# RELAYBOARD.net
KiCad netlist of a schematic drawn in Altium Designer
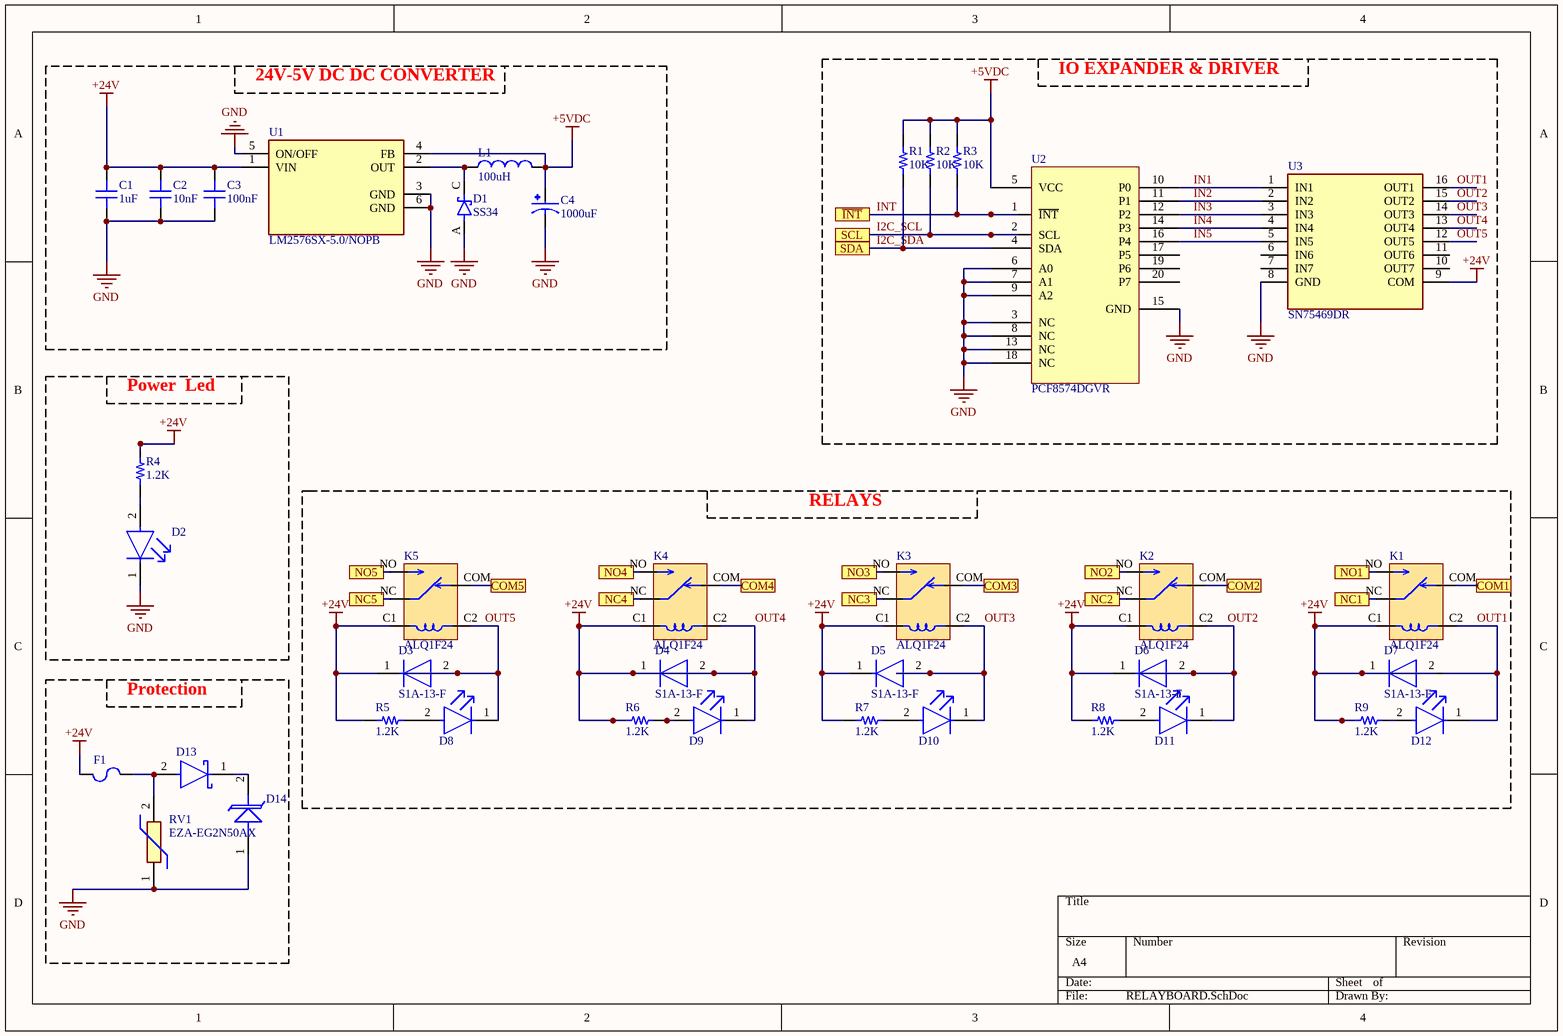
[diagram p0: RELAYBOARD.SchDoc]

(export (version "E")
  (design (tool "Eeschema 10.0.6"))
  (components
    (comp (ref "C1")
      (value "1uF")
      (footprint "CAP-0603")
      (description "Cap Ceramic 1uF 50V X5R 20% Pad SMD 0603 85C Low ESR Automotive T/R")
      (fields
        (field (name "MANUFACTURER") "Taiyo Yuden")
        (field (name "MANUFACTURER PART NUMBER") "UMK107ABJ105MAHT")
      )
      (libsource (lib "Schlib1") (part "UMK107ABJ105MAHT"))
    )
    (comp (ref "C2")
      (value "10nF")
      (footprint "CAP-0603")
      (description "Cap Ceramic 0.01uF 50V X7R 20% SMD 0603 125°C Paper T/R")
      (fields
        (field (name "MANUFACTURER") "KEMET")
        (field (name "MANUFACTURER PART NUMBER") "C0603C103M5RAC7411")
      )
      (libsource (lib "Schlib1") (part "C0603C103M5RAC7411"))
    )
    (comp (ref "C3")
      (value "100nF")
      (footprint "CAP-0603")
      (description "Cap Ceramic 0.1uF 50V X7R 10% SMD 0603 125°C Paper T/R 100nF")
      (fields
        (field (name "MANUFACTURER") "KEMET")
        (field (name "MANUFACTURER PART NUMBER") "C0603C104K5RAC7411")
      )
      (libsource (lib "Schlib1") (part "C0603C104K5RAC7411"))
    )
    (comp (ref "C4")
      (value "1000uF")
      (footprint "CAP RADIAL 1000UF")
      (description "Cap Aluminum Lytic 1000uF 25V 20% (18 X 16.5mm) SMD 0.075 Ohm 1300mA 2000h 125C Automotive T/R")
      (fields
        (field (name "MANUFACTURER") "Panasonic")
        (field (name "MANUFACTURER PART NUMBER") "EEE-TK1E102AM")
      )
      (libsource (lib "Schlib1") (part "EEETK1E102AM"))
    )
    (comp (ref "D1")
      (value "SS34")
      (footprint "SS34")
      (description "SS Series 500 mV 3 A 40 V Max Reverse Voltage Schottky Rectifier - DO-214AB")
      (fields (field (name "MANUFACTURER") "ON Semiconductor / Fairchild") (field (name "VOLTAGE") "40V"))
      (libsource (lib "Schlib1") (part "SS34"))
    )
    (comp (ref "D2")
      (value "LS R976-NR-1")
      (footprint "LS R976-NR-1")
      (description "Led SMT Red 0805 Tape")
      (fields
        (field (name "MANUFACTURER") "Osram Opto")
        (field (name "MANUFACTURER PART NUMBER") "LSR976-NR-1")
      )
      (libsource (lib "Schlib1") (part "LS R976-NR-1"))
    )
    (comp (ref "D3")
      (value "S1A-13-F")
      (footprint "S1A-13-F")
      (description "VR=50V IF=1A 10pF Trr=3us")
      (fields (field (name "MANUFACTURER") "Diodes"))
      (libsource (lib "Schlib1") (part "S1A-13-F"))
    )
    (comp (ref "D4")
      (value "S1A-13-F")
      (footprint "S1A-13-F")
      (description "VR=50V IF=1A 10pF Trr=3us")
      (fields (field (name "MANUFACTURER") "Diodes"))
      (libsource (lib "Schlib1") (part "S1A-13-F"))
    )
    (comp (ref "D5")
      (value "S1A-13-F")
      (footprint "S1A-13-F")
      (description "VR=50V IF=1A 10pF Trr=3us")
      (fields (field (name "MANUFACTURER") "Diodes"))
      (libsource (lib "Schlib1") (part "S1A-13-F"))
    )
    (comp (ref "D6")
      (value "S1A-13-F")
      (footprint "S1A-13-F")
      (description "VR=50V IF=1A 10pF Trr=3us")
      (fields (field (name "MANUFACTURER") "Diodes"))
      (libsource (lib "Schlib1") (part "S1A-13-F"))
    )
    (comp (ref "D7")
      (value "S1A-13-F")
      (footprint "S1A-13-F")
      (description "VR=50V IF=1A 10pF Trr=3us")
      (fields (field (name "MANUFACTURER") "Diodes"))
      (libsource (lib "Schlib1") (part "S1A-13-F"))
    )
    (comp (ref "D8")
      (value "LS R976-NR-1")
      (footprint "LS R976-NR-1")
      (description "Led SMT Red 0805 Tape")
      (fields
        (field (name "MANUFACTURER") "Osram Opto")
        (field (name "MANUFACTURER PART NUMBER") "LSR976-NR-1")
      )
      (libsource (lib "Schlib1") (part "LS R976-NR-1"))
    )
    (comp (ref "D9")
      (value "LS R976-NR-1")
      (footprint "LS R976-NR-1")
      (description "Led SMT Red 0805 Tape")
      (fields
        (field (name "MANUFACTURER") "Osram Opto")
        (field (name "MANUFACTURER PART NUMBER") "LSR976-NR-1")
      )
      (libsource (lib "Schlib1") (part "LS R976-NR-1"))
    )
    (comp (ref "D10")
      (value "LS R976-NR-1")
      (footprint "LS R976-NR-1")
      (description "Led SMT Red 0805 Tape")
      (fields
        (field (name "MANUFACTURER") "Osram Opto")
        (field (name "MANUFACTURER PART NUMBER") "LSR976-NR-1")
      )
      (libsource (lib "Schlib1") (part "LS R976-NR-1"))
    )
    (comp (ref "D11")
      (value "LS R976-NR-1")
      (footprint "LS R976-NR-1")
      (description "Led SMT Red 0805 Tape")
      (fields
        (field (name "MANUFACTURER") "Osram Opto")
        (field (name "MANUFACTURER PART NUMBER") "LSR976-NR-1")
      )
      (libsource (lib "Schlib1") (part "LS R976-NR-1"))
    )
    (comp (ref "D12")
      (value "LS R976-NR-1")
      (footprint "LS R976-NR-1")
      (description "Led SMT Red 0805 Tape")
      (fields
        (field (name "MANUFACTURER") "Osram Opto")
        (field (name "MANUFACTURER PART NUMBER") "LSR976-NR-1")
      )
      (libsource (lib "Schlib1") (part "LS R976-NR-1"))
    )
    (comp (ref "D13")
      (value "SS3P5-M3/84A")
      (footprint "SS3P5-M3/84A")
      (description "VISHAY   SS3P5-M3/84A   DIODE, RECTIFIER, SCHOTTKY, 3A, 50V, SMP")
      (fields (field (name "MANUFACTURER") "Vishay"))
      (libsource (lib "Schlib1") (part "SS3P5-M3/84A"))
    )
    (comp (ref "D14")
      (value "PESD1IVN27-AX")
      (footprint "PESD1IVN27-AX")
      (description "PESD1IVN27-A/SOD323/SOD2")
      (fields (field (name "MANUFACTURER") "Nexperia"))
      (libsource (lib "Schlib1") (part "PESD1IVN27-AX"))
    )
    (comp (ref "F1")
      (value "SF-1206S150-2")
      (footprint "FUSE 1206_3216 0.6MM")
      (description "FUSE BOARD MOUNT 1.5A 63VDC 1206")
      (fields (field (name "MANUFACTURER") "Bourns Inc."))
      (libsource (lib "Celestial Altium Library - altium_library") (part "MOUNTED FUSE"))
    )
    (comp (ref "K1")
      (value "ALQ1F24")
      (footprint "ALQ1F24-5")
      (fields (field (name "MANUFACTURER") "Panasonic"))
      (libsource (lib "Schlib1") (part "ALQ1F24"))
    )
    (comp (ref "K2")
      (value "ALQ1F24")
      (footprint "ALQ1F24-5")
      (fields (field (name "MANUFACTURER") "Panasonic"))
      (libsource (lib "Schlib1") (part "ALQ1F24"))
    )
    (comp (ref "K3")
      (value "ALQ1F24")
      (footprint "ALQ1F24-5")
      (fields (field (name "MANUFACTURER") "Panasonic"))
      (libsource (lib "Schlib1") (part "ALQ1F24"))
    )
    (comp (ref "K4")
      (value "ALQ1F24")
      (footprint "ALQ1F24-5")
      (fields (field (name "MANUFACTURER") "Panasonic"))
      (libsource (lib "Schlib1") (part "ALQ1F24"))
    )
    (comp (ref "K5")
      (value "ALQ1F24")
      (footprint "ALQ1F24-5")
      (fields (field (name "MANUFACTURER") "Panasonic"))
      (libsource (lib "Schlib1") (part "ALQ1F24"))
    )
    (comp (ref "L1")
      (value "100uH")
      (footprint "CBC3225T101MR")
      (description "Inductor Power Chip Wirewound 100uH 20% 100KHz Ferrite 0.34A 1.82Ohm DCR 1210 T/R")
      (fields
        (field (name "MANUFACTURER") "Taiyo Yuden")
        (field (name "MANUFACTURER PART NUMBER") "CBC3225T101MR")
      )
      (libsource (lib "Schlib1") (part "CBC3225T101MR"))
    )
    (comp (ref "R1")
      (value "10K")
      (footprint "0603")
      (description "10 kOhms ±1% 0.1W, 1/10W Chip Resistor 0603 (1608 Metric) Moisture Resistant Thick Film")
      (fields
        (field (name "MANUFACTURER") "Yageo")
        (field (name "MANUFACTURER PART NUMBER") "RC0603FR-0710KL")
      )
      (libsource (lib "Schlib1") (part "RC0603FR-0710KL"))
    )
    (comp (ref "R2")
      (value "10K")
      (footprint "0603")
      (description "10 kOhms ±1% 0.1W, 1/10W Chip Resistor 0603 (1608 Metric) Moisture Resistant Thick Film")
      (fields
        (field (name "MANUFACTURER") "Yageo")
        (field (name "MANUFACTURER PART NUMBER") "RC0603FR-0710KL")
      )
      (libsource (lib "Schlib1") (part "RC0603FR-0710KL"))
    )
    (comp (ref "R3")
      (value "10K")
      (footprint "0603")
      (description "10 kOhms ±1% 0.1W, 1/10W Chip Resistor 0603 (1608 Metric) Moisture Resistant Thick Film")
      (fields
        (field (name "MANUFACTURER") "Yageo")
        (field (name "MANUFACTURER PART NUMBER") "RC0603FR-0710KL")
      )
      (libsource (lib "Schlib1") (part "RC0603FR-0710KL"))
    )
    (comp (ref "R4")
      (value "1.2K")
      (footprint "0603")
      (description "1.2 kOhms ±5% 0.1W, 1/10W Chip Resistor 0603 (1608 Metric) Moisture Resistant Thick Film")
      (fields
        (field (name "MANUFACTURER") "Yageo")
        (field (name "MANUFACTURER PART NUMBER") "RC0402JR-071K2L")
      )
      (libsource (lib "Schlib1") (part "RC0603JR-071K2L"))
    )
    (comp (ref "R5")
      (value "1.2K")
      (footprint "0603")
      (description "1.2 kOhms ±5% 0.1W, 1/10W Chip Resistor 0603 (1608 Metric) Moisture Resistant Thick Film")
      (fields
        (field (name "MANUFACTURER") "Yageo")
        (field (name "MANUFACTURER PART NUMBER") "RC0402JR-071K2L")
      )
      (libsource (lib "Schlib1") (part "RC0603JR-071K2L"))
    )
    (comp (ref "R6")
      (value "1.2K")
      (footprint "0603")
      (description "1.2 kOhms ±5% 0.1W, 1/10W Chip Resistor 0603 (1608 Metric) Moisture Resistant Thick Film")
      (fields
        (field (name "MANUFACTURER") "Yageo")
        (field (name "MANUFACTURER PART NUMBER") "RC0402JR-071K2L")
      )
      (libsource (lib "Schlib1") (part "RC0603JR-071K2L"))
    )
    (comp (ref "R7")
      (value "1.2K")
      (footprint "0603")
      (description "1.2 kOhms ±5% 0.1W, 1/10W Chip Resistor 0603 (1608 Metric) Moisture Resistant Thick Film")
      (fields
        (field (name "MANUFACTURER") "Yageo")
        (field (name "MANUFACTURER PART NUMBER") "RC0402JR-071K2L")
      )
      (libsource (lib "Schlib1") (part "RC0603JR-071K2L"))
    )
    (comp (ref "R8")
      (value "1.2K")
      (footprint "0603")
      (description "1.2 kOhms ±5% 0.1W, 1/10W Chip Resistor 0603 (1608 Metric) Moisture Resistant Thick Film")
      (fields
        (field (name "MANUFACTURER") "Yageo")
        (field (name "MANUFACTURER PART NUMBER") "RC0402JR-071K2L")
      )
      (libsource (lib "Schlib1") (part "RC0603JR-071K2L"))
    )
    (comp (ref "R9")
      (value "1.2K")
      (footprint "0603")
      (description "1.2 kOhms ±5% 0.1W, 1/10W Chip Resistor 0603 (1608 Metric) Moisture Resistant Thick Film")
      (fields
        (field (name "MANUFACTURER") "Yageo")
        (field (name "MANUFACTURER PART NUMBER") "RC0402JR-071K2L")
      )
      (libsource (lib "Schlib1") (part "RC0603JR-071K2L"))
    )
    (comp (ref "RV1")
      (value "EZA-EG2N50AX")
      (footprint "EZA-EG2N50AX")
      (description "ESD Suppressor Diode TVS Bi-Dir 30V 2-Pin Case 0402 T/R")
      (fields (field (name "MANUFACTURER") "Panasonic"))
      (libsource (lib "Schlib1") (part "EZA-EG2N50AX"))
    )
    (comp (ref "U1")
      (value "LM2576SX-5.0/NOPB")
      (footprint "LM2576SX-5.0/NOPB")
      (description "IC REG BUCK 5V 3A TO263-5")
      (fields (field (name "MANUFACTURER") "TI National Semiconductor"))
      (libsource (lib "Schlib1") (part "LM2576SX-5.0/NOPB"))
    )
    (comp (ref "U2")
      (value "PCF8574DGVR")
      (footprint "TVSOP-20")
      (description "8-bit 2.5- to 5.5-V I2C/SMBus I/O expander with interrupt 20-TVSOP -40 to 85")
      (fields (field (name "MANUFACTURER") "Texas Instruments"))
      (libsource (lib "Schlib1") (part "PCF8574DGVR"))
    )
    (comp (ref "U3")
      (value "SN75469DR")
      (footprint "SN75469DR-SOIC16")
      (description "100-V, 7-ch darlington array with CMOS or PMOS compatibility 16-SOIC 0 to 70")
      (fields (field (name "MANUFACTURER") "Texas Instruments"))
      (libsource (lib "Schlib1") (part "SN75469DR"))
    )
  )
  (nets
    (net (code "1") (name "+5VDC") (class "Default")
      (node (ref "C4") (pin "1") (pinfunction "1_1") (pintype "passive"))
      (node (ref "L1") (pin "2") (pinfunction "2_2") (pintype "passive"))
      (node (ref "R1") (pin "2") (pinfunction "2_2") (pintype "passive"))
      (node (ref "R2") (pin "2") (pinfunction "2_2") (pintype "passive"))
      (node (ref "R3") (pin "2") (pinfunction "2_2") (pintype "passive"))
      (node (ref "U1") (pin "4") (pinfunction "FB_4") (pintype "passive"))
      (node (ref "U2") (pin "5") (pinfunction "VCC_5") (pintype "passive"))
    )
    (net (code "2") (name "+24V") (class "Default")
      (node (ref "C1") (pin "2") (pinfunction "2_2") (pintype "passive"))
      (node (ref "C2") (pin "2") (pinfunction "2_2") (pintype "passive"))
      (node (ref "C3") (pin "2") (pinfunction "2_2") (pintype "passive"))
      (node (ref "D3") (pin "1") (pinfunction "C_1") (pintype "passive"))
      (node (ref "D4") (pin "1") (pinfunction "C_1") (pintype "passive"))
      (node (ref "D4") (pin "2") (pinfunction "A_2") (pintype "passive"))
      (node (ref "D5") (pin "1") (pinfunction "C_1") (pintype "passive"))
      (node (ref "D6") (pin "1") (pinfunction "C_1") (pintype "passive"))
      (node (ref "D7") (pin "1") (pinfunction "C_1") (pintype "passive"))
      (node (ref "D9") (pin "1") (pinfunction "C_1") (pintype "passive"))
      (node (ref "F1") (pin "1") (pintype "passive"))
      (node (ref "K1") (pin "C1") (pinfunction "COIL_1_C1") (pintype "passive"))
      (node (ref "K2") (pin "C1") (pinfunction "COIL_1_C1") (pintype "passive"))
      (node (ref "K3") (pin "C1") (pinfunction "COIL_1_C1") (pintype "passive"))
      (node (ref "K4") (pin "C1") (pinfunction "COIL_1_C1") (pintype "passive"))
      (node (ref "K4") (pin "C2") (pinfunction "COIL_2_C2") (pintype "passive"))
      (node (ref "K5") (pin "C1") (pinfunction "COIL_1_C1") (pintype "passive"))
      (node (ref "R4") (pin "2") (pinfunction "2_2") (pintype "passive"))
      (node (ref "R5") (pin "1") (pinfunction "1_1") (pintype "passive"))
      (node (ref "R6") (pin "1") (pinfunction "1_1") (pintype "passive"))
      (node (ref "R7") (pin "1") (pinfunction "1_1") (pintype "passive"))
      (node (ref "R8") (pin "1") (pinfunction "1_1") (pintype "passive"))
      (node (ref "R9") (pin "1") (pinfunction "1_1") (pintype "passive"))
      (node (ref "U1") (pin "1") (pinfunction "VIN_1") (pintype "passive"))
      (node (ref "U3") (pin "13") (pinfunction "OUT4_13") (pintype "passive"))
      (node (ref "U3") (pin "9") (pinfunction "COM_9") (pintype "passive"))
    )
    (net (code "3") (name "/COM1") (class "Default")
      (node (ref "K1") (pin "COM") (pinfunction "COM_COM") (pintype "passive"))
    )
    (net (code "4") (name "/COM2") (class "Default")
      (node (ref "K2") (pin "COM") (pinfunction "COM_COM") (pintype "passive"))
    )
    (net (code "5") (name "/COM3") (class "Default")
      (node (ref "K3") (pin "COM") (pinfunction "COM_COM") (pintype "passive"))
    )
    (net (code "6") (name "/COM4") (class "Default")
      (node (ref "K4") (pin "COM") (pinfunction "COM_COM") (pintype "passive"))
    )
    (net (code "7") (name "/COM5") (class "Default")
      (node (ref "K5") (pin "COM") (pinfunction "COM_COM") (pintype "passive"))
    )
    (net (code "8") (name "/I2C_SCL") (class "Default")
      (node (ref "R2") (pin "1") (pinfunction "1_1") (pintype "passive"))
      (node (ref "U2") (pin "2") (pinfunction "SCL_2") (pintype "passive"))
    )
    (net (code "9") (name "/I2C_SDA") (class "Default")
      (node (ref "R1") (pin "1") (pinfunction "1_1") (pintype "passive"))
      (node (ref "U2") (pin "4") (pinfunction "SDA_4") (pintype "passive"))
    )
    (net (code "10") (name "/IN1") (class "Default")
      (node (ref "U2") (pin "10") (pinfunction "P0_10") (pintype "passive"))
      (node (ref "U3") (pin "1") (pinfunction "IN1_1") (pintype "passive"))
    )
    (net (code "11") (name "/IN2") (class "Default")
      (node (ref "U2") (pin "11") (pinfunction "P1_11") (pintype "passive"))
      (node (ref "U3") (pin "2") (pinfunction "IN2_2") (pintype "passive"))
    )
    (net (code "12") (name "/IN3") (class "Default")
      (node (ref "U2") (pin "12") (pinfunction "P2_12") (pintype "passive"))
      (node (ref "U3") (pin "3") (pinfunction "IN3_3") (pintype "passive"))
    )
    (net (code "13") (name "/IN4") (class "Default")
      (node (ref "U2") (pin "14") (pinfunction "P3_14") (pintype "passive"))
      (node (ref "U3") (pin "4") (pinfunction "IN4_4") (pintype "passive"))
    )
    (net (code "14") (name "/IN5") (class "Default")
      (node (ref "U2") (pin "16") (pinfunction "P4_16") (pintype "passive"))
      (node (ref "U3") (pin "5") (pinfunction "IN5_5") (pintype "passive"))
    )
    (net (code "15") (name "/INT") (class "Default")
      (node (ref "R3") (pin "1") (pinfunction "1_1") (pintype "passive"))
      (node (ref "U2") (pin "1") (pinfunction "~{INT}_1") (pintype "passive"))
    )
    (net (code "16") (name "/NC1") (class "Default")
      (node (ref "K1") (pin "NC") (pinfunction "NC_NC") (pintype "passive"))
    )
    (net (code "17") (name "/NC2") (class "Default")
      (node (ref "K2") (pin "NC") (pinfunction "NC_NC") (pintype "passive"))
    )
    (net (code "18") (name "/NC3") (class "Default")
      (node (ref "K3") (pin "NC") (pinfunction "NC_NC") (pintype "passive"))
    )
    (net (code "19") (name "/NC4") (class "Default")
      (node (ref "K4") (pin "NC") (pinfunction "NC_NC") (pintype "passive"))
    )
    (net (code "20") (name "/NC5") (class "Default")
      (node (ref "K5") (pin "NC") (pinfunction "NC_NC") (pintype "passive"))
    )
    (net (code "21") (name "/NO1") (class "Default")
      (node (ref "K1") (pin "NO") (pinfunction "NO_NO") (pintype "passive"))
    )
    (net (code "22") (name "/NO2") (class "Default")
      (node (ref "K2") (pin "NO") (pinfunction "NO_NO") (pintype "passive"))
    )
    (net (code "23") (name "/NO3") (class "Default")
      (node (ref "K3") (pin "NO") (pinfunction "NO_NO") (pintype "passive"))
    )
    (net (code "24") (name "/NO4") (class "Default")
      (node (ref "K4") (pin "NO") (pinfunction "NO_NO") (pintype "passive"))
    )
    (net (code "25") (name "/NO5") (class "Default")
      (node (ref "K5") (pin "NO") (pinfunction "NO_NO") (pintype "passive"))
    )
    (net (code "26") (name "/OUT1") (class "Default")
      (node (ref "D12") (pin "1") (pinfunction "C_1") (pintype "passive"))
      (node (ref "D7") (pin "2") (pinfunction "A_2") (pintype "passive"))
      (node (ref "K1") (pin "C2") (pinfunction "COIL_2_C2") (pintype "passive"))
      (node (ref "U3") (pin "16") (pinfunction "OUT1_16") (pintype "passive"))
    )
    (net (code "27") (name "/OUT2") (class "Default")
      (node (ref "D11") (pin "1") (pinfunction "C_1") (pintype "passive"))
      (node (ref "D6") (pin "2") (pinfunction "A_2") (pintype "passive"))
      (node (ref "K2") (pin "C2") (pinfunction "COIL_2_C2") (pintype "passive"))
      (node (ref "U3") (pin "15") (pinfunction "OUT2_15") (pintype "passive"))
    )
    (net (code "28") (name "/OUT3") (class "Default")
      (node (ref "D10") (pin "1") (pinfunction "C_1") (pintype "passive"))
      (node (ref "D5") (pin "2") (pinfunction "A_2") (pintype "passive"))
      (node (ref "K3") (pin "C2") (pinfunction "COIL_2_C2") (pintype "passive"))
      (node (ref "U3") (pin "14") (pinfunction "OUT3_14") (pintype "passive"))
    )
    (net (code "29") (name "/OUT5") (class "Default")
      (node (ref "D3") (pin "2") (pinfunction "A_2") (pintype "passive"))
      (node (ref "D8") (pin "1") (pinfunction "C_1") (pintype "passive"))
      (node (ref "K5") (pin "C2") (pinfunction "COIL_2_C2") (pintype "passive"))
      (node (ref "U3") (pin "12") (pinfunction "OUT5_12") (pintype "passive"))
    )
    (net (code "30") (name "GND") (class "Default")
      (node (ref "C1") (pin "1") (pinfunction "1_1") (pintype "passive"))
      (node (ref "C2") (pin "1") (pinfunction "1_1") (pintype "passive"))
      (node (ref "C3") (pin "1") (pinfunction "1_1") (pintype "passive"))
      (node (ref "C4") (pin "2") (pinfunction "2_2") (pintype "passive"))
      (node (ref "D1") (pin "A") (pinfunction "A_A") (pintype "passive"))
      (node (ref "D14") (pin "1") (pintype "passive"))
      (node (ref "D2") (pin "1") (pinfunction "C_1") (pintype "passive"))
      (node (ref "RV1") (pin "1") (pinfunction "1_1") (pintype "passive"))
      (node (ref "U1") (pin "3") (pinfunction "GND_3") (pintype "passive"))
      (node (ref "U1") (pin "5") (pinfunction "ON/OFF_5") (pintype "passive"))
      (node (ref "U1") (pin "6") (pinfunction "GND_6") (pintype "passive"))
      (node (ref "U2") (pin "13") (pinfunction "NC_13") (pintype "passive"))
      (node (ref "U2") (pin "15") (pinfunction "GND_15") (pintype "passive"))
      (node (ref "U2") (pin "18") (pinfunction "NC_18") (pintype "passive"))
      (node (ref "U2") (pin "3") (pinfunction "NC_3") (pintype "passive"))
      (node (ref "U2") (pin "6") (pinfunction "A0_6") (pintype "passive"))
      (node (ref "U2") (pin "7") (pinfunction "A1_7") (pintype "passive"))
      (node (ref "U2") (pin "8") (pinfunction "NC_8") (pintype "passive"))
      (node (ref "U2") (pin "9") (pinfunction "A2_9") (pintype "passive"))
      (node (ref "U3") (pin "8") (pinfunction "GND_8") (pintype "passive"))
    )
    (net (code "31") (name "Net-(D1-K)") (class "Default")
      (node (ref "D1") (pin "C") (pinfunction "K_C") (pintype "passive"))
      (node (ref "L1") (pin "1") (pinfunction "1_1") (pintype "passive"))
      (node (ref "U1") (pin "2") (pinfunction "OUT_2") (pintype "passive"))
    )
    (net (code "32") (name "Net-(D2-A)") (class "Default")
      (node (ref "D2") (pin "2") (pinfunction "A_2") (pintype "passive"))
      (node (ref "R4") (pin "1") (pinfunction "1_1") (pintype "passive"))
    )
    (net (code "33") (name "Net-(D8-A)") (class "Default")
      (node (ref "D8") (pin "2") (pinfunction "A_2") (pintype "passive"))
      (node (ref "R5") (pin "2") (pinfunction "2_2") (pintype "passive"))
    )
    (net (code "34") (name "Net-(D9-A)") (class "Default")
      (node (ref "D9") (pin "2") (pinfunction "A_2") (pintype "passive"))
      (node (ref "R6") (pin "2") (pinfunction "2_2") (pintype "passive"))
    )
    (net (code "35") (name "Net-(D10-A)") (class "Default")
      (node (ref "D10") (pin "2") (pinfunction "A_2") (pintype "passive"))
      (node (ref "R7") (pin "2") (pinfunction "2_2") (pintype "passive"))
    )
    (net (code "36") (name "Net-(D11-A)") (class "Default")
      (node (ref "D11") (pin "2") (pinfunction "A_2") (pintype "passive"))
      (node (ref "R8") (pin "2") (pinfunction "2_2") (pintype "passive"))
    )
    (net (code "37") (name "Net-(D12-A)") (class "Default")
      (node (ref "D12") (pin "2") (pinfunction "A_2") (pintype "passive"))
      (node (ref "R9") (pin "2") (pinfunction "2_2") (pintype "passive"))
    )
    (net (code "38") (name "Net-(D13-A)") (class "Default")
      (node (ref "D13") (pin "2") (pinfunction "A_2") (pintype "passive"))
      (node (ref "F1") (pin "2") (pintype "passive"))
      (node (ref "RV1") (pin "2") (pinfunction "2_2") (pintype "passive"))
    )
    (net (code "39") (name "Net-(D13-C)") (class "Default")
      (node (ref "D13") (pin "1") (pinfunction "C_1") (pintype "passive"))
      (node (ref "D14") (pin "2") (pintype "passive"))
    )
    (net (code "40") (name "unconnected-(U2-P5-Pad17)") (class "Default")
      (node (ref "U2") (pin "17") (pinfunction "P5_17") (pintype "passive"))
    )
    (net (code "41") (name "unconnected-(U2-P6-Pad19)") (class "Default")
      (node (ref "U2") (pin "19") (pinfunction "P6_19") (pintype "passive"))
    )
    (net (code "42") (name "unconnected-(U2-P7-Pad20)") (class "Default")
      (node (ref "U2") (pin "20") (pinfunction "P7_20") (pintype "passive"))
    )
    (net (code "43") (name "unconnected-(U3-IN6-Pad6)") (class "Default")
      (node (ref "U3") (pin "6") (pinfunction "IN6_6") (pintype "passive"))
    )
    (net (code "44") (name "unconnected-(U3-IN7-Pad7)") (class "Default")
      (node (ref "U3") (pin "7") (pinfunction "IN7_7") (pintype "passive"))
    )
    (net (code "45") (name "unconnected-(U3-OUT6-Pad11)") (class "Default")
      (node (ref "U3") (pin "11") (pinfunction "OUT6_11") (pintype "passive"))
    )
    (net (code "46") (name "unconnected-(U3-OUT7-Pad10)") (class "Default")
      (node (ref "U3") (pin "10") (pinfunction "OUT7_10") (pintype "passive"))
    )
  )
)
